# Illuminator.net
KiCad netlist of a schematic drawn in EAGLE
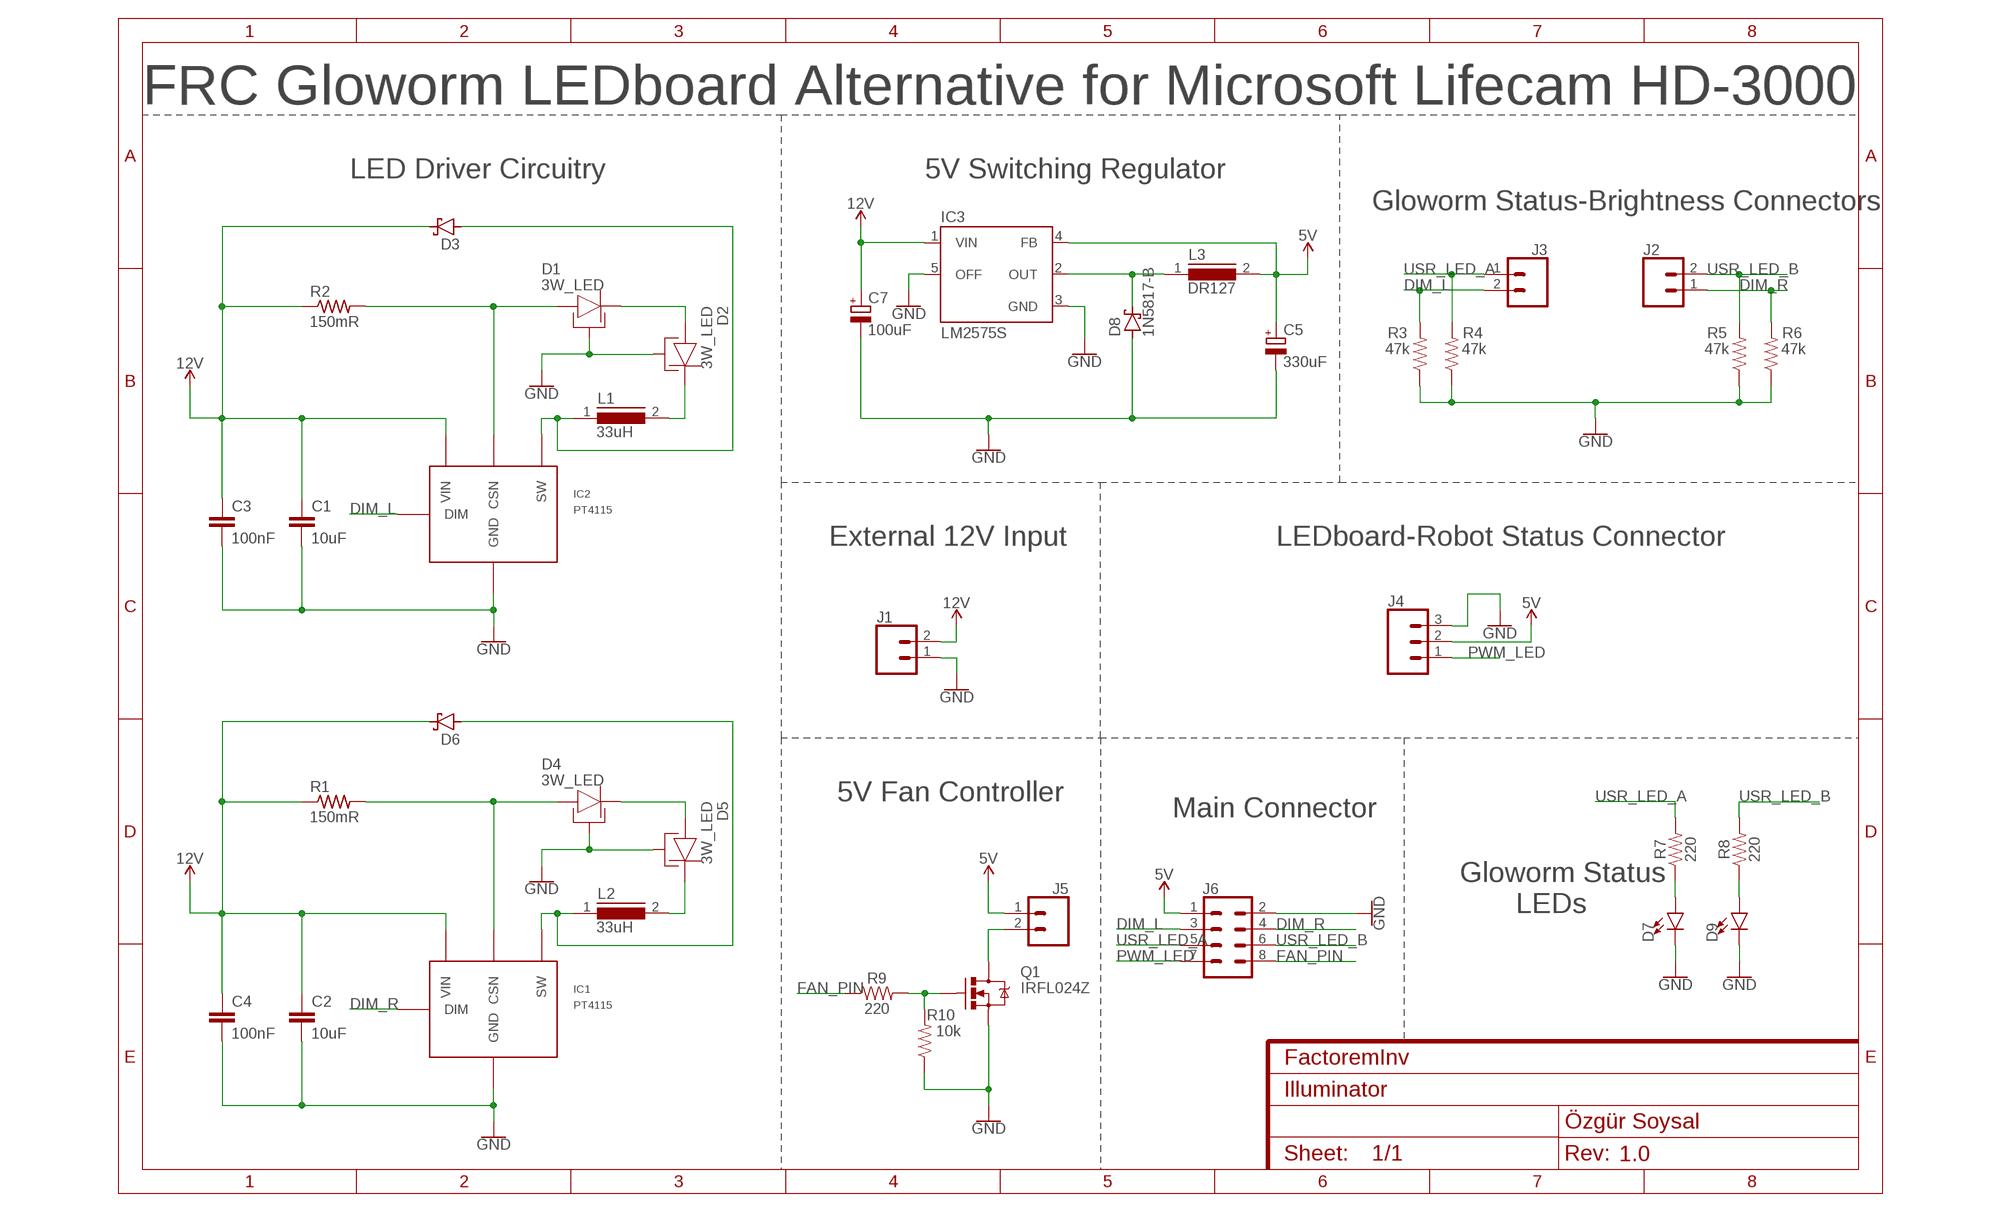
[diagram p0: schematic, sheet 1]

(export (version "E")
  (design (tool "Eeschema 10.0.6"))
  (components
    (comp (ref "C1")
      (value "10uF")
      (footprint "eagle-import:1206")
      (libsource (lib "eagle-import") (part "10UF-1206-6.3V-20%"))
    )
    (comp (ref "C2")
      (value "10uF")
      (footprint "eagle-import:1206")
      (libsource (lib "eagle-import") (part "10UF-1206-6.3V-20%"))
    )
    (comp (ref "C3")
      (value "100nF")
      (footprint "eagle-import:0805")
      (libsource (lib "eagle-import") (part "1.0UF-0805-25V-(+80/-20%)"))
    )
    (comp (ref "C4")
      (value "100nF")
      (footprint "eagle-import:0805")
      (libsource (lib "eagle-import") (part "1.0UF-0805-25V-(+80/-20%)"))
    )
    (comp (ref "C5")
      (value "330uF")
      (footprint "eagle-import:CAPAE1030X1050N")
      (libsource (lib "eagle-import") (part "C-POLECAP-10.5MM_"))
    )
    (comp (ref "C7")
      (value "100uF")
      (footprint "eagle-import:CAPAE830X1050N")
      (libsource (lib "eagle-import") (part "C-POLECAP-8.5MM_"))
    )
    (comp (ref "D1")
      (value "3W_LED")
      (footprint "eagle-import:3W_LED")
      (libsource (lib "eagle-import") (part "3W_LED"))
    )
    (comp (ref "D2")
      (value "3W_LED")
      (footprint "eagle-import:3W_LED")
      (libsource (lib "eagle-import") (part "3W_LED"))
    )
    (comp (ref "D3")
      (value "SCHOTTKY-DIODESMD")
      (footprint "eagle-import:SMB")
      (libsource (lib "eagle-import") (part "SCHOTTKY-DIODESMD"))
    )
    (comp (ref "D4")
      (value "3W_LED")
      (footprint "eagle-import:3W_LED")
      (libsource (lib "eagle-import") (part "3W_LED"))
    )
    (comp (ref "D5")
      (value "3W_LED")
      (footprint "eagle-import:3W_LED")
      (libsource (lib "eagle-import") (part "3W_LED"))
    )
    (comp (ref "D6")
      (value "SCHOTTKY-DIODESMD")
      (footprint "eagle-import:SMB")
      (libsource (lib "eagle-import") (part "SCHOTTKY-DIODESMD"))
    )
    (comp (ref "D7")
      (value "LED1206")
      (footprint "eagle-import:LED-1206")
      (libsource (lib "eagle-import") (part "LED1206"))
    )
    (comp (ref "D8")
      (value "1N5817-B")
      (footprint "eagle-import:DO41-7.6")
      (libsource (lib "eagle-import") (part "1N5817-B"))
    )
    (comp (ref "D9")
      (value "LED1206")
      (footprint "eagle-import:LED-1206")
      (libsource (lib "eagle-import") (part "LED1206"))
    )
    (comp (ref "IC1")
      (value "PT4115")
      (footprint "eagle-import:PT4115")
      (libsource (lib "eagle-import") (part "PT4115"))
    )
    (comp (ref "IC2")
      (value "PT4115")
      (footprint "eagle-import:PT4115")
      (libsource (lib "eagle-import") (part "PT4115"))
    )
    (comp (ref "IC3")
      (value "LM2575S")
      (footprint "eagle-import:TO263-5")
      (libsource (lib "eagle-import") (part "LM2575S"))
    )
    (comp (ref "J1")
      (value "CONN_02SPRING-2.54-RA")
      (footprint "eagle-import:SPRINGTERMINAL-2.54MM-2")
      (libsource (lib "eagle-import") (part "CONN_02SPRING-2.54-RA"))
    )
    (comp (ref "J2")
      (value "CONN_02")
      (footprint "eagle-import:1X02")
      (libsource (lib "eagle-import") (part "CONN_02"))
    )
    (comp (ref "J3")
      (value "CONN_02")
      (footprint "eagle-import:1X02")
      (libsource (lib "eagle-import") (part "CONN_02"))
    )
    (comp (ref "J4")
      (value "CONN_03")
      (footprint "eagle-import:1X03")
      (libsource (lib "eagle-import") (part "CONN_03"))
    )
    (comp (ref "J5")
      (value "CONN_02")
      (footprint "eagle-import:1X02")
      (libsource (lib "eagle-import") (part "CONN_02"))
    )
    (comp (ref "J6")
      (value "CONN_04X2")
      (footprint "eagle-import:2X4")
      (libsource (lib "eagle-import") (part "CONN_04X2"))
    )
    (comp (ref "L1")
      (value "33uH")
      (footprint "eagle-import:DR125")
      (libsource (lib "eagle-import") (part "DR125"))
    )
    (comp (ref "L2")
      (value "33uH")
      (footprint "eagle-import:DR125")
      (libsource (lib "eagle-import") (part "DR125"))
    )
    (comp (ref "L3")
      (value "DR127")
      (footprint "eagle-import:DR127")
      (libsource (lib "eagle-import") (part "DR127"))
    )
    (comp (ref "Q1")
      (value "IRFL024Z")
      (footprint "eagle-import:SOT-223")
      (libsource (lib "eagle-import") (part "MOSFET-NCHANNEL-SOT-223"))
    )
    (comp (ref "R1")
      (value "150mR")
      (footprint "eagle-import:R2512")
      (libsource (lib "eagle-import") (part "R-US_R2512"))
    )
    (comp (ref "R2")
      (value "150mR")
      (footprint "eagle-import:R2512")
      (libsource (lib "eagle-import") (part "R-US_R2512"))
    )
    (comp (ref "R3")
      (value "47k")
      (footprint "eagle-import:0805")
      (libsource (lib "eagle-import") (part "RESISTOR0805"))
    )
    (comp (ref "R4")
      (value "47k")
      (footprint "eagle-import:0805")
      (libsource (lib "eagle-import") (part "RESISTOR0805"))
    )
    (comp (ref "R5")
      (value "47k")
      (footprint "eagle-import:0805")
      (libsource (lib "eagle-import") (part "RESISTOR0805"))
    )
    (comp (ref "R6")
      (value "47k")
      (footprint "eagle-import:0805")
      (libsource (lib "eagle-import") (part "RESISTOR0805"))
    )
    (comp (ref "R7")
      (value "220")
      (footprint "eagle-import:1206")
      (libsource (lib "eagle-import") (part "RESISTOR1206"))
    )
    (comp (ref "R8")
      (value "220")
      (footprint "eagle-import:1206")
      (libsource (lib "eagle-import") (part "RESISTOR1206"))
    )
    (comp (ref "R9")
      (value "220")
      (footprint "eagle-import:1206")
      (libsource (lib "eagle-import") (part "RESISTOR1206"))
    )
    (comp (ref "R10")
      (value "10k")
      (footprint "eagle-import:1206")
      (libsource (lib "eagle-import") (part "RESISTOR1206"))
    )
  )
  (nets
    (net (code "1") (name "/DIM_L") (class "Default")
      (node (ref "IC2") (pin "3") (pinfunction "DIM_3") (pintype "bidirectional"))
      (node (ref "J3") (pin "2") (pinfunction "2_2") (pintype "passive"))
      (node (ref "J6") (pin "3") (pinfunction "3_3") (pintype "passive"))
      (node (ref "R3") (pin "2") (pinfunction "2_2") (pintype "passive"))
    )
    (net (code "2") (name "/DIM_R") (class "Default")
      (node (ref "IC1") (pin "3") (pinfunction "DIM_3") (pintype "bidirectional"))
      (node (ref "J2") (pin "1") (pinfunction "1_1") (pintype "passive"))
      (node (ref "J6") (pin "4") (pinfunction "4_4") (pintype "passive"))
      (node (ref "R6") (pin "2") (pinfunction "2_2") (pintype "passive"))
    )
    (net (code "3") (name "/FAN_PIN") (class "Default")
      (node (ref "J6") (pin "8") (pinfunction "8_8") (pintype "passive"))
      (node (ref "R9") (pin "1") (pinfunction "1_1") (pintype "passive"))
    )
    (net (code "4") (name "/PWM_LED") (class "Default")
      (node (ref "J4") (pin "1") (pinfunction "1_1") (pintype "passive"))
      (node (ref "J6") (pin "7") (pinfunction "7_7") (pintype "passive"))
    )
    (net (code "5") (name "/USR_LED_A") (class "Default")
      (node (ref "J3") (pin "1") (pinfunction "1_1") (pintype "passive"))
      (node (ref "J6") (pin "5") (pinfunction "5_5") (pintype "passive"))
      (node (ref "R4") (pin "2") (pinfunction "2_2") (pintype "passive"))
      (node (ref "R7") (pin "2") (pinfunction "2_2") (pintype "passive"))
    )
    (net (code "6") (name "/USR_LED_B") (class "Default")
      (node (ref "J2") (pin "2") (pinfunction "2_2") (pintype "passive"))
      (node (ref "J6") (pin "6") (pinfunction "6_6") (pintype "passive"))
      (node (ref "R5") (pin "2") (pinfunction "2_2") (pintype "passive"))
      (node (ref "R8") (pin "2") (pinfunction "2_2") (pintype "passive"))
    )
    (net (code "7") (name "5V") (class "Default")
      (node (ref "C5") (pin "1") (pinfunction "+_1") (pintype "passive"))
      (node (ref "IC3") (pin "4") (pinfunction "FB_4") (pintype "input"))
      (node (ref "J4") (pin "2") (pinfunction "2_2") (pintype "passive"))
      (node (ref "J5") (pin "1") (pinfunction "1_1") (pintype "passive"))
      (node (ref "J6") (pin "1") (pinfunction "1_1") (pintype "passive"))
      (node (ref "L3") (pin "2") (pinfunction "2_2") (pintype "passive"))
    )
    (net (code "8") (name "12V") (class "Default")
      (node (ref "C1") (pin "1") (pinfunction "1_1") (pintype "passive"))
      (node (ref "C2") (pin "1") (pinfunction "1_1") (pintype "passive"))
      (node (ref "C3") (pin "1") (pinfunction "1_1") (pintype "passive"))
      (node (ref "C4") (pin "1") (pinfunction "1_1") (pintype "passive"))
      (node (ref "C7") (pin "1") (pinfunction "+_1") (pintype "passive"))
      (node (ref "D3") (pin "C") (pinfunction "C_C") (pintype "passive"))
      (node (ref "D6") (pin "C") (pinfunction "C_C") (pintype "passive"))
      (node (ref "IC1") (pin "5") (pinfunction "VIN_5") (pintype "bidirectional"))
      (node (ref "IC2") (pin "5") (pinfunction "VIN_5") (pintype "bidirectional"))
      (node (ref "IC3") (pin "1") (pinfunction "VIN_1") (pintype "power_in"))
      (node (ref "J1") (pin "2") (pinfunction "2_2") (pintype "passive"))
      (node (ref "R1") (pin "1") (pinfunction "1_1") (pintype "passive"))
      (node (ref "R2") (pin "1") (pinfunction "1_1") (pintype "passive"))
    )
    (net (code "9") (name "GND") (class "Default")
      (node (ref "C1") (pin "2") (pinfunction "2_2") (pintype "passive"))
      (node (ref "C2") (pin "2") (pinfunction "2_2") (pintype "passive"))
      (node (ref "C3") (pin "2") (pinfunction "2_2") (pintype "passive"))
      (node (ref "C4") (pin "2") (pinfunction "2_2") (pintype "passive"))
      (node (ref "C5") (pin "2") (pinfunction "-_2") (pintype "passive"))
      (node (ref "C7") (pin "2") (pinfunction "-_2") (pintype "passive"))
      (node (ref "D1") (pin "B_PAD") (pinfunction "B_PAD_B_PAD") (pintype "bidirectional"))
      (node (ref "D2") (pin "B_PAD") (pinfunction "B_PAD_B_PAD") (pintype "bidirectional"))
      (node (ref "D4") (pin "B_PAD") (pinfunction "B_PAD_B_PAD") (pintype "bidirectional"))
      (node (ref "D5") (pin "B_PAD") (pinfunction "B_PAD_B_PAD") (pintype "bidirectional"))
      (node (ref "D7") (pin "C") (pinfunction "C_C") (pintype "passive"))
      (node (ref "D8") (pin "A") (pinfunction "A_A") (pintype "passive"))
      (node (ref "D9") (pin "C") (pinfunction "C_C") (pintype "passive"))
      (node (ref "IC1") (pin "2") (pinfunction "GND_2") (pintype "power_in"))
      (node (ref "IC1") (pin "2A") (pinfunction "GND_2A") (pintype "power_in"))
      (node (ref "IC2") (pin "2") (pinfunction "GND_2") (pintype "power_in"))
      (node (ref "IC2") (pin "2A") (pinfunction "GND_2A") (pintype "power_in"))
      (node (ref "IC3") (pin "3") (pinfunction "GND_3") (pintype "power_in"))
      (node (ref "IC3") (pin "5") (pinfunction "OFF_5") (pintype "input"))
      (node (ref "J1") (pin "1") (pinfunction "1_1") (pintype "passive"))
      (node (ref "J4") (pin "3") (pinfunction "3_3") (pintype "passive"))
      (node (ref "J6") (pin "2") (pinfunction "2_2") (pintype "passive"))
      (node (ref "Q1") (pin "3") (pinfunction "S_3") (pintype "passive"))
      (node (ref "R10") (pin "1") (pinfunction "1_1") (pintype "passive"))
      (node (ref "R3") (pin "1") (pinfunction "1_1") (pintype "passive"))
      (node (ref "R4") (pin "1") (pinfunction "1_1") (pintype "passive"))
      (node (ref "R5") (pin "1") (pinfunction "1_1") (pintype "passive"))
      (node (ref "R6") (pin "1") (pinfunction "1_1") (pintype "passive"))
    )
    (net (code "10") (name "Net-(D1-PadCATHODE)") (class "Default")
      (node (ref "D1") (pin "CATHODE") (pinfunction "CATHODE_CATHODE") (pintype "bidirectional"))
      (node (ref "D2") (pin "ANODE") (pinfunction "ANODE_ANODE") (pintype "bidirectional"))
    )
    (net (code "11") (name "Net-(D2-PadCATHODE)") (class "Default")
      (node (ref "D2") (pin "CATHODE") (pinfunction "CATHODE_CATHODE") (pintype "bidirectional"))
      (node (ref "L1") (pin "2") (pinfunction "2_2") (pintype "passive"))
    )
    (net (code "12") (name "Net-(D4-PadCATHODE)") (class "Default")
      (node (ref "D4") (pin "CATHODE") (pinfunction "CATHODE_CATHODE") (pintype "bidirectional"))
      (node (ref "D5") (pin "ANODE") (pinfunction "ANODE_ANODE") (pintype "bidirectional"))
    )
    (net (code "13") (name "Net-(D5-PadCATHODE)") (class "Default")
      (node (ref "D5") (pin "CATHODE") (pinfunction "CATHODE_CATHODE") (pintype "bidirectional"))
      (node (ref "L2") (pin "2") (pinfunction "2_2") (pintype "passive"))
    )
    (net (code "14") (name "Net-(D7-PadA)") (class "Default")
      (node (ref "D7") (pin "A") (pinfunction "A_A") (pintype "passive"))
      (node (ref "R7") (pin "1") (pinfunction "1_1") (pintype "passive"))
    )
    (net (code "15") (name "Net-(D9-PadA)") (class "Default")
      (node (ref "D9") (pin "A") (pinfunction "A_A") (pintype "passive"))
      (node (ref "R8") (pin "1") (pinfunction "1_1") (pintype "passive"))
    )
    (net (code "16") (name "Net-(IC1-CSN)") (class "Default")
      (node (ref "D4") (pin "ANODE") (pinfunction "ANODE_ANODE") (pintype "bidirectional"))
      (node (ref "IC1") (pin "4") (pinfunction "CSN_4") (pintype "bidirectional"))
      (node (ref "R1") (pin "2") (pinfunction "2_2") (pintype "passive"))
    )
    (net (code "17") (name "Net-(IC1-SW)") (class "Default")
      (node (ref "D6") (pin "A") (pinfunction "A_A") (pintype "passive"))
      (node (ref "IC1") (pin "1") (pinfunction "SW_1") (pintype "bidirectional"))
      (node (ref "L2") (pin "1") (pinfunction "1_1") (pintype "passive"))
    )
    (net (code "18") (name "Net-(IC2-CSN)") (class "Default")
      (node (ref "D1") (pin "ANODE") (pinfunction "ANODE_ANODE") (pintype "bidirectional"))
      (node (ref "IC2") (pin "4") (pinfunction "CSN_4") (pintype "bidirectional"))
      (node (ref "R2") (pin "2") (pinfunction "2_2") (pintype "passive"))
    )
    (net (code "19") (name "Net-(IC2-SW)") (class "Default")
      (node (ref "D3") (pin "A") (pinfunction "A_A") (pintype "passive"))
      (node (ref "IC2") (pin "1") (pinfunction "SW_1") (pintype "bidirectional"))
      (node (ref "L1") (pin "1") (pinfunction "1_1") (pintype "passive"))
    )
    (net (code "20") (name "Net-(IC3-OUT)") (class "Default")
      (node (ref "D8") (pin "C") (pinfunction "C_C") (pintype "passive"))
      (node (ref "IC3") (pin "2") (pinfunction "OUT_2") (pintype "output"))
      (node (ref "L3") (pin "1") (pinfunction "1_1") (pintype "passive"))
    )
    (net (code "21") (name "Net-(J5-Pad2)") (class "Default")
      (node (ref "J5") (pin "2") (pinfunction "2_2") (pintype "passive"))
      (node (ref "Q1") (pin "2") (pinfunction "D_2") (pintype "passive"))
      (node (ref "Q1") (pin "4") (pinfunction "D_4") (pintype "passive"))
    )
    (net (code "22") (name "Net-(Q1-G)") (class "Default")
      (node (ref "Q1") (pin "1") (pinfunction "G_1") (pintype "passive"))
      (node (ref "R10") (pin "2") (pinfunction "2_2") (pintype "passive"))
      (node (ref "R9") (pin "2") (pinfunction "2_2") (pintype "passive"))
    )
  )
)
